# Sheet1.net
KiCad netlist of a schematic drawn in Altium Designer
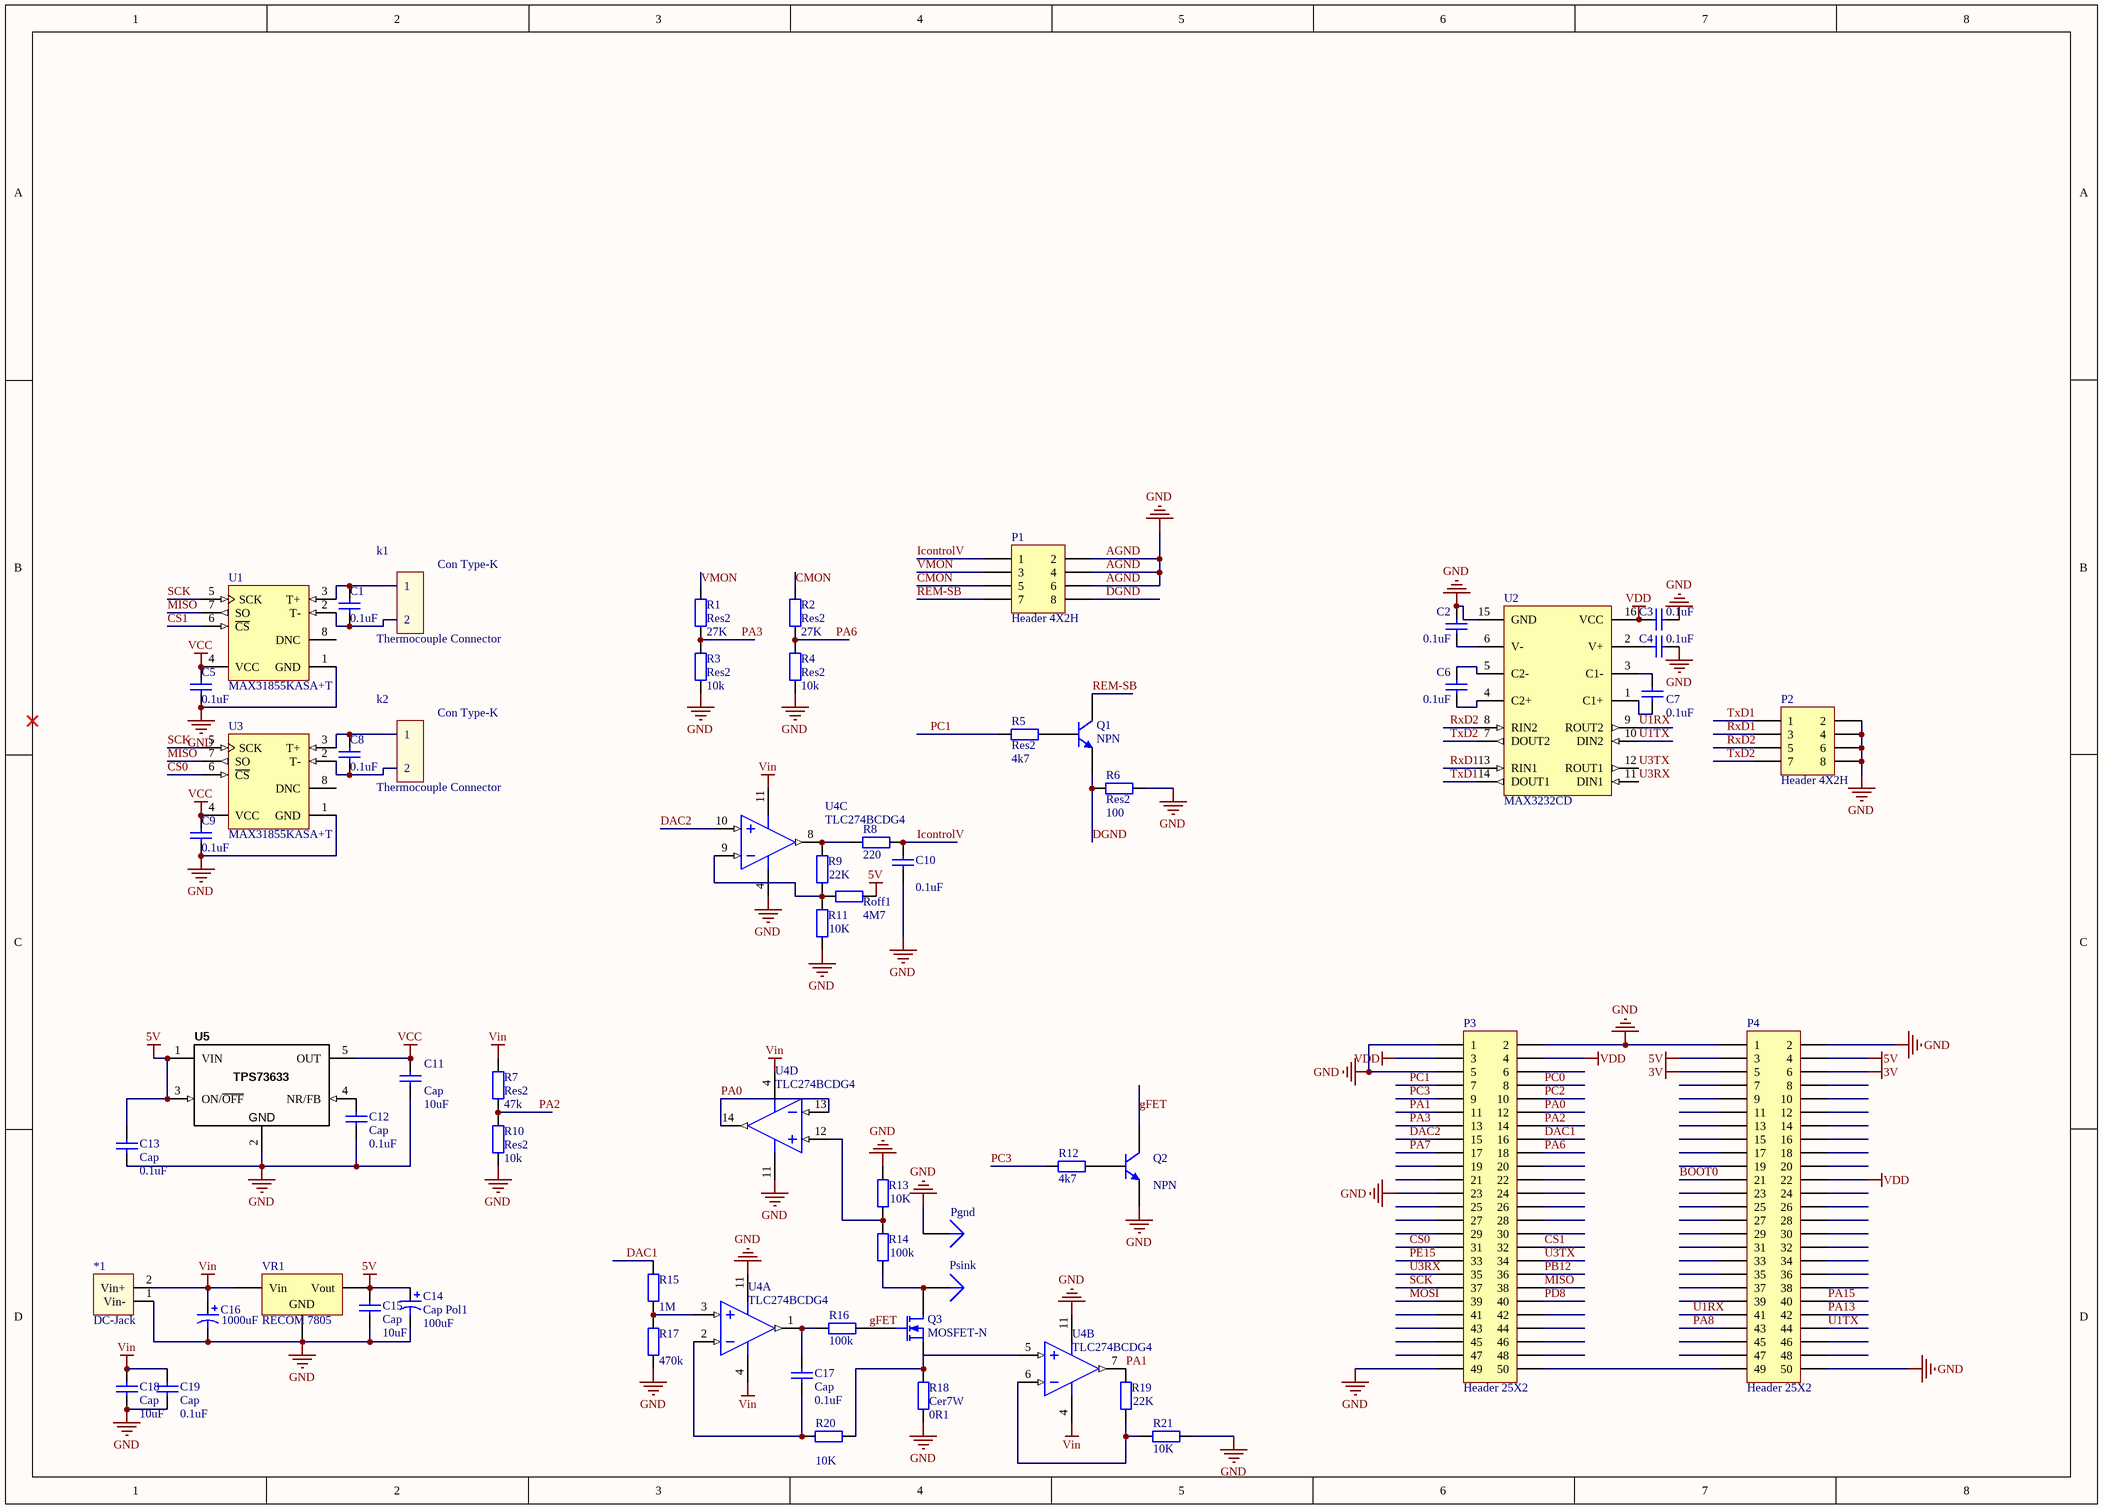
[diagram p0: Sheet1.SchDoc]

(export (version "E")
  (design (tool "Eeschema 10.0.6"))
  (components
    (comp (ref "*1")
      (value "DC-Jack")
      (footprint "DC-Jack")
      (libsource (lib "SchematicLib") (part "DC-Jack"))
    )
    (comp (ref "C1")
      (value "0.1uF")
      (footprint "CAPC2012X135N")
      (description "Capacitor")
      (fields (field (name "Comment") "Cap") (field (name "PUBLISHER") "Altium Limited"))
      (libsource (lib "Miscellaneous Devices") (part "Cap"))
    )
    (comp (ref "C2")
      (value "0.1uF")
      (footprint "CAPC2012X135N")
      (description "Capacitor")
      (fields (field (name "Comment") "Cap") (field (name "PUBLISHER") "Altium Limited"))
      (libsource (lib "Miscellaneous Devices") (part "Cap"))
    )
    (comp (ref "C3")
      (value "0.1uF")
      (footprint "CAPC2012X135N")
      (description "Capacitor")
      (fields (field (name "Comment") "Cap") (field (name "PUBLISHER") "Altium Limited"))
      (libsource (lib "Miscellaneous Devices") (part "Cap"))
    )
    (comp (ref "C4")
      (value "0.1uF")
      (footprint "CAPC2012X135N")
      (description "Capacitor")
      (fields (field (name "Comment") "Cap") (field (name "PUBLISHER") "Altium Limited"))
      (libsource (lib "Miscellaneous Devices") (part "Cap"))
    )
    (comp (ref "C5")
      (value "0.1uF")
      (footprint "CAPC2012X135N")
      (description "Capacitor")
      (fields (field (name "Comment") "Cap") (field (name "PUBLISHER") "Altium Limited"))
      (libsource (lib "Miscellaneous Devices") (part "Cap"))
    )
    (comp (ref "C6")
      (value "0.1uF")
      (footprint "CAPC2012X135N")
      (description "Capacitor")
      (fields (field (name "Comment") "Cap") (field (name "PUBLISHER") "Altium Limited"))
      (libsource (lib "Miscellaneous Devices") (part "Cap"))
    )
    (comp (ref "C7")
      (value "0.1uF")
      (footprint "CAPC2012X135N")
      (description "Capacitor")
      (fields (field (name "Comment") "Cap") (field (name "PUBLISHER") "Altium Limited"))
      (libsource (lib "Miscellaneous Devices") (part "Cap"))
    )
    (comp (ref "C8")
      (value "0.1uF")
      (footprint "CAPC2012X135N")
      (description "Capacitor")
      (fields (field (name "Comment") "Cap") (field (name "PUBLISHER") "Altium Limited"))
      (libsource (lib "Miscellaneous Devices") (part "Cap"))
    )
    (comp (ref "C9")
      (value "0.1uF")
      (footprint "CAPC2012X135N")
      (description "Capacitor")
      (fields (field (name "Comment") "Cap") (field (name "PUBLISHER") "Altium Limited"))
      (libsource (lib "Miscellaneous Devices") (part "Cap"))
    )
    (comp (ref "C10")
      (value "0.1uF")
      (footprint "CAPC2012X135N")
      (description "Capacitor")
      (fields (field (name "Comment") "Cap") (field (name "PUBLISHER") "Altium Limited"))
      (libsource (lib "Miscellaneous Devices") (part "Cap"))
    )
    (comp (ref "C11")
      (value "Cap")
      (footprint "CAPC2012X135N")
      (description "Capacitor")
      (fields (field (name "ALTIUM_VALUE") "10uF") (field (name "PUBLISHER") "Altium Limited"))
      (libsource (lib "Miscellaneous Devices") (part "Cap"))
    )
    (comp (ref "C12")
      (value "Cap")
      (footprint "CAPC2012X135N")
      (description "Capacitor")
      (fields (field (name "ALTIUM_VALUE") "0.1uF") (field (name "PUBLISHER") "Altium Limited"))
      (libsource (lib "Miscellaneous Devices") (part "Cap"))
    )
    (comp (ref "C13")
      (value "Cap")
      (footprint "CAPC2012X135N")
      (description "Capacitor")
      (fields (field (name "ALTIUM_VALUE") "0.1uF") (field (name "PUBLISHER") "Altium Limited"))
      (libsource (lib "Miscellaneous Devices") (part "Cap"))
    )
    (comp (ref "C14")
      (value "Cap Pol1")
      (footprint "RB7.6-15")
      (description "Polarized Capacitor (Radial)")
      (fields (field (name "ALTIUM_VALUE") "100uF") (field (name "PUBLISHER") "Altium Limited"))
      (libsource (lib "Miscellaneous Devices") (part "Cap Pol1"))
    )
    (comp (ref "C15")
      (value "Cap")
      (footprint "CAPC2012X135N")
      (description "Capacitor")
      (fields (field (name "ALTIUM_VALUE") "10uF") (field (name "PUBLISHER") "Altium Limited"))
      (libsource (lib "Miscellaneous Devices") (part "Cap"))
    )
    (comp (ref "C16")
      (value "1000uF")
      (footprint "RB7.6-15")
      (description "Polarized Capacitor (Radial)")
      (fields (field (name "Comment") "Cap Pol1") (field (name "PUBLISHER") "Altium Limited"))
      (libsource (lib "Miscellaneous Devices") (part "Cap Pol1"))
    )
    (comp (ref "C17")
      (value "Cap")
      (footprint "CAPC2012X135N")
      (description "Capacitor")
      (fields (field (name "ALTIUM_VALUE") "0.1uF") (field (name "PUBLISHER") "Altium Limited"))
      (libsource (lib "Miscellaneous Devices") (part "Cap"))
    )
    (comp (ref "C18")
      (value "Cap")
      (footprint "CAPC2012X135N")
      (description "Capacitor")
      (fields (field (name "ALTIUM_VALUE") "10uF") (field (name "PUBLISHER") "Altium Limited"))
      (libsource (lib "Miscellaneous Devices") (part "Cap"))
    )
    (comp (ref "C19")
      (value "Cap")
      (footprint "CAPC2012X135N")
      (description "Capacitor")
      (fields (field (name "ALTIUM_VALUE") "0.1uF") (field (name "PUBLISHER") "Altium Limited"))
      (libsource (lib "Miscellaneous Devices") (part "Cap"))
    )
    (comp (ref "k1")
      (value "Thermocouple Connector")
      (footprint "K-Type Thermocouple Connector")
      (libsource (lib "SchematicLib") (part "Thermocouple Connector"))
    )
    (comp (ref "k2")
      (value "Thermocouple Connector")
      (footprint "K-Type Thermocouple Connector")
      (libsource (lib "SchematicLib") (part "Thermocouple Connector"))
    )
    (comp (ref "P1")
      (value "Header 4X2H")
      (footprint "CON8")
      (description "Header, 4-Pin, Dual row, Right Angle")
      (fields (field (name "PUBLISHER") "Altium Limited"))
      (libsource (lib "Miscellaneous Connectors") (part "Header 4X2H"))
    )
    (comp (ref "P2")
      (value "Header 4X2H")
      (footprint "CON8")
      (description "Header, 4-Pin, Dual row, Right Angle")
      (fields (field (name "PUBLISHER") "Altium Limited"))
      (libsource (lib "Miscellaneous Connectors") (part "Header 4X2H"))
    )
    (comp (ref "P3")
      (value "Header 25X2")
      (footprint "HDR2X25")
      (description "Header, 25-Pin, Dual row")
      (fields (field (name "PUBLISHER") "Altium Limited"))
      (libsource (lib "Miscellaneous Connectors") (part "Header 25X2"))
    )
    (comp (ref "P4")
      (value "Header 25X2")
      (footprint "HDR2X25")
      (description "Header, 25-Pin, Dual row")
      (fields (field (name "PUBLISHER") "Altium Limited"))
      (libsource (lib "Miscellaneous Connectors") (part "Header 25X2"))
    )
    (comp (ref "Pgnd")
      (value "Plug")
      (footprint "PIN1")
      (fields (field (name "PUBLISHER") "Altium Limited"))
      (libsource (lib "Miscellaneous Connectors") (part "Plug"))
    )
    (comp (ref "Psink")
      (value "Plug")
      (footprint "PIN1")
      (fields (field (name "PUBLISHER") "Altium Limited"))
      (libsource (lib "Miscellaneous Connectors") (part "Plug"))
    )
    (comp (ref "Q1")
      (value "NPN")
      (footprint "SOT-23_N")
      (description "NPN Bipolar Transistor")
      (fields (field (name "PUBLISHER") "Altium Limited"))
      (libsource (lib "Miscellaneous Devices") (part "NPN"))
    )
    (comp (ref "Q2")
      (value "NPN")
      (footprint "SOT-23_N")
      (description "NPN Bipolar Transistor")
      (fields (field (name "PUBLISHER") "Altium Limited"))
      (libsource (lib "Miscellaneous Devices") (part "NPN"))
    )
    (comp (ref "Q3")
      (value "MOSFET-N")
      (footprint "TO-220-AB")
      (description "N-Channel MOSFET")
      (fields (field (name "PUBLISHER") "Altium Limited"))
      (libsource (lib "Miscellaneous Devices") (part "MOSFET-N"))
    )
    (comp (ref "R1")
      (value "Res2")
      (footprint "RESC2012X70N")
      (description "Resistor")
      (fields (field (name "ALTIUM_VALUE") "27K") (field (name "PUBLISHER") "Altium Limited"))
      (libsource (lib "Miscellaneous Devices") (part "Res2"))
    )
    (comp (ref "R2")
      (value "Res2")
      (footprint "RESC2012X70N")
      (description "Resistor")
      (fields (field (name "ALTIUM_VALUE") "27K") (field (name "PUBLISHER") "Altium Limited"))
      (libsource (lib "Miscellaneous Devices") (part "Res2"))
    )
    (comp (ref "R3")
      (value "Res2")
      (footprint "RESC2012X70N")
      (description "Resistor")
      (fields (field (name "ALTIUM_VALUE") "10k") (field (name "PUBLISHER") "Altium Limited"))
      (libsource (lib "Miscellaneous Devices") (part "Res2"))
    )
    (comp (ref "R4")
      (value "Res2")
      (footprint "RESC2012X70N")
      (description "Resistor")
      (fields (field (name "ALTIUM_VALUE") "10k") (field (name "PUBLISHER") "Altium Limited"))
      (libsource (lib "Miscellaneous Devices") (part "Res2"))
    )
    (comp (ref "R5")
      (value "Res2")
      (footprint "RESC2012X70N")
      (description "Resistor")
      (fields (field (name "ALTIUM_VALUE") "4k7") (field (name "PUBLISHER") "Altium Limited"))
      (libsource (lib "") (part "Res2_1"))
    )
    (comp (ref "R6")
      (value "Res2")
      (footprint "RESC2012X70N")
      (description "Resistor")
      (fields (field (name "ALTIUM_VALUE") "100") (field (name "PUBLISHER") "Altium Limited"))
      (libsource (lib "") (part "Res2_1"))
    )
    (comp (ref "R7")
      (value "Res2")
      (footprint "RESC2012X70N")
      (description "Resistor")
      (fields (field (name "ALTIUM_VALUE") "47k") (field (name "PUBLISHER") "Altium Limited"))
      (libsource (lib "Miscellaneous Devices") (part "Res2"))
    )
    (comp (ref "R8")
      (value "220")
      (footprint "RESC2012X70N")
      (description "Resistor")
      (fields (field (name "Comment") "Res2") (field (name "PUBLISHER") "Altium Limited"))
      (libsource (lib "") (part "Res2_2"))
    )
    (comp (ref "R9")
      (value "22K")
      (footprint "RESC2012X70N")
      (description "Resistor")
      (fields (field (name "Comment") "Res2") (field (name "PUBLISHER") "Altium Limited"))
      (libsource (lib "Miscellaneous Devices") (part "Res2"))
    )
    (comp (ref "R10")
      (value "Res2")
      (footprint "RESC2012X70N")
      (description "Resistor")
      (fields (field (name "ALTIUM_VALUE") "10k") (field (name "PUBLISHER") "Altium Limited"))
      (libsource (lib "Miscellaneous Devices") (part "Res2"))
    )
    (comp (ref "R11")
      (value "10K")
      (footprint "RESC2012X70N")
      (description "Resistor")
      (fields (field (name "Comment") "Res2") (field (name "PUBLISHER") "Altium Limited"))
      (libsource (lib "Miscellaneous Devices") (part "Res2"))
    )
    (comp (ref "R12")
      (value "4k7")
      (footprint "RESC2012X70N")
      (description "Resistor")
      (fields (field (name "Comment") "Res2") (field (name "PUBLISHER") "Altium Limited"))
      (libsource (lib "") (part "Res2_1"))
    )
    (comp (ref "R13")
      (value "10K")
      (footprint "RESC2012X70N")
      (description "Resistor")
      (fields (field (name "Comment") "Res2") (field (name "PUBLISHER") "Altium Limited"))
      (libsource (lib "Miscellaneous Devices") (part "Res2"))
    )
    (comp (ref "R14")
      (value "100k")
      (footprint "RESC2012X70N")
      (description "Resistor")
      (fields (field (name "Comment") "Res2") (field (name "PUBLISHER") "Altium Limited"))
      (libsource (lib "Miscellaneous Devices") (part "Res2"))
    )
    (comp (ref "R15")
      (value "1M")
      (footprint "RESC2012X70N")
      (description "Resistor")
      (fields (field (name "Comment") "Res2") (field (name "PUBLISHER") "Altium Limited"))
      (libsource (lib "Miscellaneous Devices") (part "Res2"))
    )
    (comp (ref "R16")
      (value "100k")
      (footprint "RESC2012X70N")
      (description "Resistor")
      (fields (field (name "Comment") "Res2") (field (name "PUBLISHER") "Altium Limited"))
      (libsource (lib "") (part "Res2_2"))
    )
    (comp (ref "R17")
      (value "470k")
      (footprint "RESC2012X70N")
      (description "Resistor")
      (fields (field (name "Comment") "Res2") (field (name "PUBLISHER") "Altium Limited"))
      (libsource (lib "Miscellaneous Devices") (part "Res2"))
    )
    (comp (ref "R18")
      (value "Cer7W")
      (footprint "Cer7W")
      (description "Resistor")
      (fields (field (name "ALTIUM_VALUE") "0R1") (field (name "PUBLISHER") "Altium Limited"))
      (libsource (lib "Miscellaneous Devices") (part "Res2"))
    )
    (comp (ref "R19")
      (value "22K")
      (footprint "RESC2012X70N")
      (description "Resistor")
      (fields (field (name "Comment") "Res2") (field (name "PUBLISHER") "Altium Limited"))
      (libsource (lib "Miscellaneous Devices") (part "Res2"))
    )
    (comp (ref "R20")
      (value "10K")
      (footprint "RESC2012X70N")
      (description "Resistor")
      (fields (field (name "Comment") "Res2") (field (name "PUBLISHER") "Altium Limited"))
      (libsource (lib "") (part "Res2_2"))
    )
    (comp (ref "R21")
      (value "10K")
      (footprint "RESC2012X70N")
      (description "Resistor")
      (fields (field (name "Comment") "Res2") (field (name "PUBLISHER") "Altium Limited"))
      (libsource (lib "") (part "Res2_1"))
    )
    (comp (ref "Roff1")
      (value "4M7")
      (footprint "RESC2012X70N")
      (description "Resistor")
      (fields (field (name "Comment") "Res2") (field (name "PUBLISHER") "Altium Limited"))
      (libsource (lib "") (part "Res2_1"))
    )
    (comp (ref "U1")
      (value "MAX31855KASA+T")
      (footprint "MAXM-S8+4_N")
      (fields (field (name "GENERIC PART NUMBER") "MAX31855"))
      (libsource (lib "Maxim Sensors") (part "MAX31855KASA+T"))
    )
    (comp (ref "U2")
      (value "MAX3232CD")
      (footprint "TI-D16_N")
      (libsource (lib "Texas Instruments Interface RS-232") (part "MAX3232CD"))
    )
    (comp (ref "U3")
      (value "MAX31855KASA+T")
      (footprint "MAXM-S8+4_N")
      (fields (field (name "GENERIC PART NUMBER") "MAX31855"))
      (libsource (lib "Maxim Sensors") (part "MAX31855KASA+T"))
    )
    (comp (ref "U4")
      (value "TLC274BCDG4")
      (footprint "TI-D14_N")
      (fields (field (name "MANUFACTURER") "Texas Instruments"))
      (libsource (lib "TI Amplifiers and Linear Operational Amplifier General Purpose") (part "TLC274BCDG4"))
    )
    (comp (ref "U5")
      (value "3.3V")
      (footprint "SOT23-5")
      (description "IC LDO Regulator 3.3V 400mA SOT23-5 SMD")
      (fields (field (name "TOLERANCE") "±0.5%"))
      (libsource (lib "PBL - Regulators") (part "LinREG_3V3_400mA_TPS73633DBV"))
    )
    (comp (ref "VR1")
      (value "RECOM 7805")
      (footprint "Recom78xx")
      (description "Voltage Regulator")
      (fields (field (name "PUBLISHER") "Altium Limited"))
      (libsource (lib "SchematicLib") (part "Volt Reg"))
    )
  )
  (nets
    (net (code "1") (name "/BOOT0") (class "Default")
      (node (ref "P4") (pin "21") (pinfunction "21_21") (pintype "passive"))
    )
    (net (code "2") (name "/CMON") (class "Default")
      (node (ref "P1") (pin "5") (pinfunction "5_5") (pintype "passive"))
      (node (ref "R2") (pin "2") (pinfunction "2_2") (pintype "passive"))
    )
    (net (code "3") (name "/CS0") (class "Default")
      (node (ref "P3") (pin "31") (pinfunction "31_31") (pintype "passive"))
      (node (ref "U3") (pin "6") (pinfunction "~{CS}_6") (pintype "input"))
    )
    (net (code "4") (name "/CS1") (class "Default")
      (node (ref "P3") (pin "32") (pinfunction "32_32") (pintype "passive"))
      (node (ref "U1") (pin "6") (pinfunction "~{CS}_6") (pintype "input"))
    )
    (net (code "5") (name "/DAC1") (class "Default")
      (node (ref "P3") (pin "16") (pinfunction "16_16") (pintype "passive"))
      (node (ref "R15") (pin "2") (pinfunction "2_2") (pintype "passive"))
    )
    (net (code "6") (name "/DAC2") (class "Default")
      (node (ref "P3") (pin "15") (pinfunction "15_15") (pintype "passive"))
      (node (ref "U4") (pin "10") (pinfunction "IN3+_10") (pintype "input"))
    )
    (net (code "7") (name "/DGND") (class "Default")
      (node (ref "P1") (pin "8") (pinfunction "8_8") (pintype "passive"))
      (node (ref "Q1") (pin "3") (pinfunction "E_3") (pintype "passive"))
      (node (ref "R6") (pin "2") (pinfunction "2_2") (pintype "passive"))
    )
    (net (code "8") (name "/IcontrolV") (class "Default")
      (node (ref "C10") (pin "2") (pinfunction "2_2") (pintype "passive"))
      (node (ref "P1") (pin "1") (pinfunction "1_1") (pintype "passive"))
      (node (ref "R8") (pin "2") (pinfunction "2_2") (pintype "passive"))
    )
    (net (code "9") (name "/MISO") (class "Default")
      (node (ref "P3") (pin "38") (pinfunction "38_38") (pintype "passive"))
      (node (ref "U1") (pin "7") (pinfunction "SO_7") (pintype "output"))
      (node (ref "U3") (pin "7") (pinfunction "SO_7") (pintype "output"))
    )
    (net (code "10") (name "/MOSI") (class "Default")
      (node (ref "P3") (pin "39") (pinfunction "39_39") (pintype "passive"))
    )
    (net (code "11") (name "/PA0") (class "Default")
      (node (ref "P3") (pin "12") (pinfunction "12_12") (pintype "passive"))
      (node (ref "U4") (pin "13") (pinfunction "IN4-_13") (pintype "input"))
      (node (ref "U4") (pin "14") (pinfunction "OUT4_14") (pintype "output"))
    )
    (net (code "12") (name "/PA1") (class "Default")
      (node (ref "P3") (pin "11") (pinfunction "11_11") (pintype "passive"))
      (node (ref "R19") (pin "2") (pinfunction "2_2") (pintype "passive"))
      (node (ref "U4") (pin "7") (pinfunction "OUT2_7") (pintype "output"))
    )
    (net (code "13") (name "/PA2") (class "Default")
      (node (ref "P3") (pin "14") (pinfunction "14_14") (pintype "passive"))
      (node (ref "R10") (pin "2") (pinfunction "2_2") (pintype "passive"))
      (node (ref "R7") (pin "1") (pinfunction "1_1") (pintype "passive"))
    )
    (net (code "14") (name "/PA3") (class "Default")
      (node (ref "P3") (pin "13") (pinfunction "13_13") (pintype "passive"))
      (node (ref "R1") (pin "1") (pinfunction "1_1") (pintype "passive"))
      (node (ref "R3") (pin "2") (pinfunction "2_2") (pintype "passive"))
    )
    (net (code "15") (name "/PA6") (class "Default")
      (node (ref "P3") (pin "18") (pinfunction "18_18") (pintype "passive"))
      (node (ref "R2") (pin "1") (pinfunction "1_1") (pintype "passive"))
      (node (ref "R4") (pin "2") (pinfunction "2_2") (pintype "passive"))
    )
    (net (code "16") (name "/PA7") (class "Default")
      (node (ref "P3") (pin "17") (pinfunction "17_17") (pintype "passive"))
    )
    (net (code "17") (name "/PA8") (class "Default")
      (node (ref "P4") (pin "43") (pinfunction "43_43") (pintype "passive"))
    )
    (net (code "18") (name "/PA13") (class "Default")
      (node (ref "P4") (pin "42") (pinfunction "42_42") (pintype "passive"))
    )
    (net (code "19") (name "/PA15") (class "Default")
      (node (ref "P4") (pin "40") (pinfunction "40_40") (pintype "passive"))
    )
    (net (code "20") (name "/PB12") (class "Default")
      (node (ref "P3") (pin "36") (pinfunction "36_36") (pintype "passive"))
    )
    (net (code "21") (name "/PC0") (class "Default")
      (node (ref "P3") (pin "8") (pinfunction "8_8") (pintype "passive"))
    )
    (net (code "22") (name "/PC1") (class "Default")
      (node (ref "P3") (pin "7") (pinfunction "7_7") (pintype "passive"))
      (node (ref "R5") (pin "2") (pinfunction "2_2") (pintype "passive"))
    )
    (net (code "23") (name "/PC2") (class "Default")
      (node (ref "P3") (pin "10") (pinfunction "10_10") (pintype "passive"))
    )
    (net (code "24") (name "/PC3") (class "Default")
      (node (ref "P3") (pin "9") (pinfunction "9_9") (pintype "passive"))
      (node (ref "R12") (pin "2") (pinfunction "2_2") (pintype "passive"))
    )
    (net (code "25") (name "/PD8") (class "Default")
      (node (ref "P3") (pin "40") (pinfunction "40_40") (pintype "passive"))
    )
    (net (code "26") (name "/PE15") (class "Default")
      (node (ref "P3") (pin "33") (pinfunction "33_33") (pintype "passive"))
    )
    (net (code "27") (name "/REM-SB") (class "Default")
      (node (ref "P1") (pin "7") (pinfunction "7_7") (pintype "passive"))
      (node (ref "Q1") (pin "1") (pinfunction "C_1") (pintype "passive"))
    )
    (net (code "28") (name "/RxD1") (class "Default")
      (node (ref "P2") (pin "3") (pinfunction "3_3") (pintype "passive"))
      (node (ref "U2") (pin "13") (pinfunction "RIN1_13") (pintype "input"))
    )
    (net (code "29") (name "/RxD2") (class "Default")
      (node (ref "P2") (pin "5") (pinfunction "5_5") (pintype "passive"))
      (node (ref "U2") (pin "8") (pinfunction "RIN2_8") (pintype "input"))
    )
    (net (code "30") (name "/SCK") (class "Default")
      (node (ref "P3") (pin "37") (pinfunction "37_37") (pintype "passive"))
      (node (ref "U1") (pin "5") (pinfunction "SCK_5") (pintype "input"))
      (node (ref "U3") (pin "5") (pinfunction "SCK_5") (pintype "input"))
    )
    (net (code "31") (name "/TxD1") (class "Default")
      (node (ref "P2") (pin "1") (pinfunction "1_1") (pintype "passive"))
      (node (ref "U2") (pin "14") (pinfunction "DOUT1_14") (pintype "output"))
    )
    (net (code "32") (name "/TxD2") (class "Default")
      (node (ref "P2") (pin "7") (pinfunction "7_7") (pintype "passive"))
      (node (ref "U2") (pin "7") (pinfunction "DOUT2_7") (pintype "output"))
    )
    (net (code "33") (name "/U1RX") (class "Default")
      (node (ref "P4") (pin "41") (pinfunction "41_41") (pintype "passive"))
      (node (ref "U2") (pin "9") (pinfunction "ROUT2_9") (pintype "output"))
    )
    (net (code "34") (name "/U1TX") (class "Default")
      (node (ref "P4") (pin "44") (pinfunction "44_44") (pintype "passive"))
      (node (ref "U2") (pin "10") (pinfunction "DIN2_10") (pintype "input"))
    )
    (net (code "35") (name "/U3RX") (class "Default")
      (node (ref "P3") (pin "35") (pinfunction "35_35") (pintype "passive"))
      (node (ref "U2") (pin "11") (pinfunction "DIN1_11") (pintype "input"))
    )
    (net (code "36") (name "/U3TX") (class "Default")
      (node (ref "P3") (pin "34") (pinfunction "34_34") (pintype "passive"))
      (node (ref "U2") (pin "12") (pinfunction "ROUT1_12") (pintype "output"))
    )
    (net (code "37") (name "/VMON") (class "Default")
      (node (ref "P1") (pin "3") (pinfunction "3_3") (pintype "passive"))
      (node (ref "R1") (pin "2") (pinfunction "2_2") (pintype "passive"))
    )
    (net (code "38") (name "/gFET") (class "Default")
      (node (ref "Q2") (pin "1") (pinfunction "C_1") (pintype "passive"))
      (node (ref "Q3") (pin "2") (pinfunction "G_2") (pintype "passive"))
      (node (ref "R16") (pin "2") (pinfunction "2_2") (pintype "passive"))
    )
    (net (code "39") (name "3V") (class "Default")
      (node (ref "P4") (pin "5") (pinfunction "5_5") (pintype "passive"))
      (node (ref "P4") (pin "6") (pinfunction "6_6") (pintype "passive"))
    )
    (net (code "40") (name "5V") (class "Default")
      (node (ref "C13") (pin "2") (pinfunction "2_2") (pintype "passive"))
      (node (ref "C14") (pin "1") (pinfunction "1_1") (pintype "passive"))
      (node (ref "C15") (pin "2") (pinfunction "2_2") (pintype "passive"))
      (node (ref "P4") (pin "3") (pinfunction "3_3") (pintype "passive"))
      (node (ref "P4") (pin "4") (pinfunction "4_4") (pintype "passive"))
      (node (ref "Roff1") (pin "1") (pinfunction "1_1") (pintype "passive"))
      (node (ref "U5") (pin "1") (pinfunction "VIN_1") (pintype "power_in"))
      (node (ref "U5") (pin "3") (pinfunction "ON/~{OFF}_3") (pintype "input"))
      (node (ref "VR1") (pin "3") (pinfunction "Vout_3") (pintype "passive"))
    )
    (net (code "41") (name "GND") (class "Default")
      (node (ref "*1") (pin "1") (pinfunction "Vin-_1") (pintype "passive"))
      (node (ref "C10") (pin "1") (pinfunction "1_1") (pintype "passive"))
      (node (ref "C11") (pin "1") (pinfunction "1_1") (pintype "passive"))
      (node (ref "C12") (pin "1") (pinfunction "1_1") (pintype "passive"))
      (node (ref "C13") (pin "1") (pinfunction "1_1") (pintype "passive"))
      (node (ref "C14") (pin "2") (pinfunction "2_2") (pintype "passive"))
      (node (ref "C15") (pin "1") (pinfunction "1_1") (pintype "passive"))
      (node (ref "C16") (pin "2") (pinfunction "2_2") (pintype "passive"))
      (node (ref "C18") (pin "1") (pinfunction "1_1") (pintype "passive"))
      (node (ref "C19") (pin "1") (pinfunction "1_1") (pintype "passive"))
      (node (ref "C2") (pin "2") (pinfunction "2_2") (pintype "passive"))
      (node (ref "C3") (pin "1") (pinfunction "1_1") (pintype "passive"))
      (node (ref "C4") (pin "1") (pinfunction "1_1") (pintype "passive"))
      (node (ref "C5") (pin "1") (pinfunction "1_1") (pintype "passive"))
      (node (ref "C9") (pin "1") (pinfunction "1_1") (pintype "passive"))
      (node (ref "P1") (pin "2") (pinfunction "2_2") (pintype "passive"))
      (node (ref "P1") (pin "4") (pinfunction "4_4") (pintype "passive"))
      (node (ref "P1") (pin "6") (pinfunction "6_6") (pintype "passive"))
      (node (ref "P2") (pin "2") (pinfunction "2_2") (pintype "passive"))
      (node (ref "P2") (pin "4") (pinfunction "4_4") (pintype "passive"))
      (node (ref "P2") (pin "6") (pinfunction "6_6") (pintype "passive"))
      (node (ref "P2") (pin "8") (pinfunction "8_8") (pintype "passive"))
      (node (ref "P3") (pin "1") (pinfunction "1_1") (pintype "passive"))
      (node (ref "P3") (pin "2") (pinfunction "2_2") (pintype "passive"))
      (node (ref "P3") (pin "23") (pinfunction "23_23") (pintype "passive"))
      (node (ref "P3") (pin "49") (pinfunction "49_49") (pintype "passive"))
      (node (ref "P3") (pin "5") (pinfunction "5_5") (pintype "passive"))
      (node (ref "P4") (pin "1") (pinfunction "1_1") (pintype "passive"))
      (node (ref "P4") (pin "2") (pinfunction "2_2") (pintype "passive"))
      (node (ref "P4") (pin "50") (pinfunction "50_50") (pintype "passive"))
      (node (ref "Pgnd") (pin "1") (pinfunction "1_1") (pintype "passive"))
      (node (ref "Q2") (pin "3") (pinfunction "E_3") (pintype "passive"))
      (node (ref "R10") (pin "1") (pinfunction "1_1") (pintype "passive"))
      (node (ref "R11") (pin "1") (pinfunction "1_1") (pintype "passive"))
      (node (ref "R13") (pin "2") (pinfunction "2_2") (pintype "passive"))
      (node (ref "R17") (pin "1") (pinfunction "1_1") (pintype "passive"))
      (node (ref "R18") (pin "1") (pinfunction "1_1") (pintype "passive"))
      (node (ref "R21") (pin "1") (pinfunction "1_1") (pintype "passive"))
      (node (ref "R3") (pin "1") (pinfunction "1_1") (pintype "passive"))
      (node (ref "R4") (pin "1") (pinfunction "1_1") (pintype "passive"))
      (node (ref "R6") (pin "1") (pinfunction "1_1") (pintype "passive"))
      (node (ref "U1") (pin "1") (pinfunction "GND_1") (pintype "power_in"))
      (node (ref "U2") (pin "15") (pinfunction "GND_15") (pintype "power_in"))
      (node (ref "U3") (pin "1") (pinfunction "GND_1") (pintype "power_in"))
      (node (ref "U4") (pin "11") (pinfunction "GND_11") (pintype "power_in"))
      (node (ref "U4") (pin "4") (pinfunction "VDD_4") (pintype "power_in"))
      (node (ref "U5") (pin "2") (pinfunction "GND_2") (pintype "power_in"))
      (node (ref "VR1") (pin "2") (pinfunction "GND_2") (pintype "passive"))
    )
    (net (code "42") (name "Net-(P3-Pad50)") (class "Default")
      (node (ref "P3") (pin "50") (pinfunction "50_50") (pintype "passive"))
      (node (ref "P4") (pin "49") (pinfunction "49_49") (pintype "passive"))
    )
    (net (code "43") (name "Net-(Q1-B)") (class "Default")
      (node (ref "Q1") (pin "2") (pinfunction "B_2") (pintype "passive"))
      (node (ref "R5") (pin "1") (pinfunction "1_1") (pintype "passive"))
    )
    (net (code "44") (name "Net-(Q2-B)") (class "Default")
      (node (ref "Q2") (pin "2") (pinfunction "B_2") (pintype "passive"))
      (node (ref "R12") (pin "1") (pinfunction "1_1") (pintype "passive"))
    )
    (net (code "45") (name "Net-(Q3-D)") (class "Default")
      (node (ref "Psink") (pin "1") (pinfunction "1_1") (pintype "passive"))
      (node (ref "Q3") (pin "1") (pinfunction "D_1") (pintype "passive"))
      (node (ref "R14") (pin "1") (pinfunction "1_1") (pintype "passive"))
    )
    (net (code "46") (name "Net-(Q3-S)") (class "Default")
      (node (ref "Q3") (pin "3") (pinfunction "S_3") (pintype "passive"))
      (node (ref "R18") (pin "2") (pinfunction "2_2") (pintype "passive"))
      (node (ref "R20") (pin "2") (pinfunction "2_2") (pintype "passive"))
      (node (ref "U4") (pin "5") (pinfunction "IN2+_5") (pintype "input"))
    )
    (net (code "47") (name "Net-(U1-T+)") (class "Default")
      (node (ref "C1") (pin "2") (pinfunction "2_2") (pintype "passive"))
      (node (ref "U1") (pin "3") (pinfunction "T+_3") (pintype "input"))
      (node (ref "k1") (pin "1") (pinfunction "1_1") (pintype "passive"))
    )
    (net (code "48") (name "Net-(U1-T-)") (class "Default")
      (node (ref "C1") (pin "1") (pinfunction "1_1") (pintype "passive"))
      (node (ref "U1") (pin "2") (pinfunction "T-_2") (pintype "input"))
      (node (ref "k1") (pin "2") (pinfunction "2_2") (pintype "passive"))
    )
    (net (code "49") (name "Net-(U2-C1+)") (class "Default")
      (node (ref "C7") (pin "1") (pinfunction "1_1") (pintype "passive"))
      (node (ref "U2") (pin "1") (pinfunction "C1+_1") (pintype "passive"))
    )
    (net (code "50") (name "Net-(U2-C1-)") (class "Default")
      (node (ref "C7") (pin "2") (pinfunction "2_2") (pintype "passive"))
      (node (ref "U2") (pin "3") (pinfunction "C1-_3") (pintype "passive"))
    )
    (net (code "51") (name "Net-(U2-C2+)") (class "Default")
      (node (ref "C6") (pin "1") (pinfunction "1_1") (pintype "passive"))
      (node (ref "U2") (pin "4") (pinfunction "C2+_4") (pintype "passive"))
    )
    (net (code "52") (name "Net-(U2-C2-)") (class "Default")
      (node (ref "C6") (pin "2") (pinfunction "2_2") (pintype "passive"))
      (node (ref "U2") (pin "5") (pinfunction "C2-_5") (pintype "passive"))
    )
    (net (code "53") (name "Net-(U2-V+)") (class "Default")
      (node (ref "C4") (pin "2") (pinfunction "2_2") (pintype "passive"))
      (node (ref "U2") (pin "2") (pinfunction "V+_2") (pintype "power_in"))
    )
    (net (code "54") (name "Net-(U2-V-)") (class "Default")
      (node (ref "C2") (pin "1") (pinfunction "1_1") (pintype "passive"))
      (node (ref "U2") (pin "6") (pinfunction "V-_6") (pintype "power_in"))
    )
    (net (code "55") (name "Net-(U3-T+)") (class "Default")
      (node (ref "C8") (pin "2") (pinfunction "2_2") (pintype "passive"))
      (node (ref "U3") (pin "3") (pinfunction "T+_3") (pintype "input"))
      (node (ref "k2") (pin "1") (pinfunction "1_1") (pintype "passive"))
    )
    (net (code "56") (name "Net-(U3-T-)") (class "Default")
      (node (ref "C8") (pin "1") (pinfunction "1_1") (pintype "passive"))
      (node (ref "U3") (pin "2") (pinfunction "T-_2") (pintype "input"))
      (node (ref "k2") (pin "2") (pinfunction "2_2") (pintype "passive"))
    )
    (net (code "57") (name "Net-(U4A-IN1+)") (class "Default")
      (node (ref "R15") (pin "1") (pinfunction "1_1") (pintype "passive"))
      (node (ref "R17") (pin "2") (pinfunction "2_2") (pintype "passive"))
      (node (ref "U4") (pin "3") (pinfunction "IN1+_3") (pintype "input"))
    )
    (net (code "58") (name "Net-(U4A-IN1-)") (class "Default")
      (node (ref "C17") (pin "1") (pinfunction "1_1") (pintype "passive"))
      (node (ref "R20") (pin "1") (pinfunction "1_1") (pintype "passive"))
      (node (ref "U4") (pin "2") (pinfunction "IN1-_2") (pintype "input"))
    )
    (net (code "59") (name "Net-(U4A-OUT1)") (class "Default")
      (node (ref "C17") (pin "2") (pinfunction "2_2") (pintype "passive"))
      (node (ref "R16") (pin "1") (pinfunction "1_1") (pintype "passive"))
      (node (ref "U4") (pin "1") (pinfunction "OUT1_1") (pintype "output"))
    )
    (net (code "60") (name "Net-(U4B-IN2-)") (class "Default")
      (node (ref "R19") (pin "1") (pinfunction "1_1") (pintype "passive"))
      (node (ref "R21") (pin "2") (pinfunction "2_2") (pintype "passive"))
      (node (ref "U4") (pin "6") (pinfunction "IN2-_6") (pintype "input"))
    )
    (net (code "61") (name "Net-(U4C-IN3-)") (class "Default")
      (node (ref "R11") (pin "2") (pinfunction "2_2") (pintype "passive"))
      (node (ref "R9") (pin "1") (pinfunction "1_1") (pintype "passive"))
      (node (ref "Roff1") (pin "2") (pinfunction "2_2") (pintype "passive"))
      (node (ref "U4") (pin "9") (pinfunction "IN3-_9") (pintype "input"))
    )
    (net (code "62") (name "Net-(U4C-OUT3)") (class "Default")
      (node (ref "R8") (pin "1") (pinfunction "1_1") (pintype "passive"))
      (node (ref "R9") (pin "2") (pinfunction "2_2") (pintype "passive"))
      (node (ref "U4") (pin "8") (pinfunction "OUT3_8") (pintype "output"))
    )
    (net (code "63") (name "Net-(U4D-IN4+)") (class "Default")
      (node (ref "R13") (pin "1") (pinfunction "1_1") (pintype "passive"))
      (node (ref "R14") (pin "2") (pinfunction "2_2") (pintype "passive"))
      (node (ref "U4") (pin "12") (pinfunction "IN4+_12") (pintype "input"))
    )
    (net (code "64") (name "Net-(U5-NR{slash}FB)") (class "Default")
      (node (ref "C12") (pin "2") (pinfunction "2_2") (pintype "passive"))
      (node (ref "U5") (pin "4") (pinfunction "NR/FB_4") (pintype "input"))
    )
    (net (code "65") (name "VCC") (class "Default")
      (node (ref "C11") (pin "2") (pinfunction "2_2") (pintype "passive"))
      (node (ref "C5") (pin "2") (pinfunction "2_2") (pintype "passive"))
      (node (ref "C9") (pin "2") (pinfunction "2_2") (pintype "passive"))
      (node (ref "U1") (pin "4") (pinfunction "VCC_4") (pintype "power_in"))
      (node (ref "U3") (pin "4") (pinfunction "VCC_4") (pintype "power_in"))
      (node (ref "U5") (pin "5") (pinfunction "OUT_5") (pintype "power_in"))
    )
    (net (code "66") (name "VDD") (class "Default")
      (node (ref "C3") (pin "2") (pinfunction "2_2") (pintype "passive"))
      (node (ref "P3") (pin "3") (pinfunction "3_3") (pintype "passive"))
      (node (ref "P3") (pin "4") (pinfunction "4_4") (pintype "passive"))
      (node (ref "P4") (pin "22") (pinfunction "22_22") (pintype "passive"))
      (node (ref "U2") (pin "16") (pinfunction "VCC_16") (pintype "power_in"))
    )
    (net (code "67") (name "Vin") (class "Default")
      (node (ref "*1") (pin "2") (pinfunction "Vin+_2") (pintype "passive"))
      (node (ref "C16") (pin "1") (pinfunction "1_1") (pintype "passive"))
      (node (ref "C18") (pin "2") (pinfunction "2_2") (pintype "passive"))
      (node (ref "C19") (pin "2") (pinfunction "2_2") (pintype "passive"))
      (node (ref "R7") (pin "2") (pinfunction "2_2") (pintype "passive"))
      (node (ref "U4") (pin "11") (pinfunction "GND_11") (pintype "power_in"))
      (node (ref "U4") (pin "4") (pinfunction "VDD_4") (pintype "power_in"))
      (node (ref "VR1") (pin "1") (pinfunction "Vin_1") (pintype "passive"))
    )
    (net (code "68") (name "unconnected-(P3-Pad6)") (class "Default")
      (node (ref "P3") (pin "6") (pinfunction "6_6") (pintype "passive"))
    )
    (net (code "69") (name "unconnected-(P3-Pad19)") (class "Default")
      (node (ref "P3") (pin "19") (pinfunction "19_19") (pintype "passive"))
    )
    (net (code "70") (name "unconnected-(P3-Pad20)") (class "Default")
      (node (ref "P3") (pin "20") (pinfunction "20_20") (pintype "passive"))
    )
    (net (code "71") (name "unconnected-(P3-Pad21)") (class "Default")
      (node (ref "P3") (pin "21") (pinfunction "21_21") (pintype "passive"))
    )
    (net (code "72") (name "unconnected-(P3-Pad22)") (class "Default")
      (node (ref "P3") (pin "22") (pinfunction "22_22") (pintype "passive"))
    )
    (net (code "73") (name "unconnected-(P3-Pad24)") (class "Default")
      (node (ref "P3") (pin "24") (pinfunction "24_24") (pintype "passive"))
    )
    (net (code "74") (name "unconnected-(P3-Pad25)") (class "Default")
      (node (ref "P3") (pin "25") (pinfunction "25_25") (pintype "passive"))
    )
    (net (code "75") (name "unconnected-(P3-Pad26)") (class "Default")
      (node (ref "P3") (pin "26") (pinfunction "26_26") (pintype "passive"))
    )
    (net (code "76") (name "unconnected-(P3-Pad27)") (class "Default")
      (node (ref "P3") (pin "27") (pinfunction "27_27") (pintype "passive"))
    )
    (net (code "77") (name "unconnected-(P3-Pad28)") (class "Default")
      (node (ref "P3") (pin "28") (pinfunction "28_28") (pintype "passive"))
    )
    (net (code "78") (name "unconnected-(P3-Pad29)") (class "Default")
      (node (ref "P3") (pin "29") (pinfunction "29_29") (pintype "passive"))
    )
    (net (code "79") (name "unconnected-(P3-Pad30)") (class "Default")
      (node (ref "P3") (pin "30") (pinfunction "30_30") (pintype "passive"))
    )
    (net (code "80") (name "unconnected-(P3-Pad41)") (class "Default")
      (node (ref "P3") (pin "41") (pinfunction "41_41") (pintype "passive"))
    )
    (net (code "81") (name "unconnected-(P3-Pad42)") (class "Default")
      (node (ref "P3") (pin "42") (pinfunction "42_42") (pintype "passive"))
    )
    (net (code "82") (name "unconnected-(P3-Pad43)") (class "Default")
      (node (ref "P3") (pin "43") (pinfunction "43_43") (pintype "passive"))
    )
    (net (code "83") (name "unconnected-(P3-Pad44)") (class "Default")
      (node (ref "P3") (pin "44") (pinfunction "44_44") (pintype "passive"))
    )
    (net (code "84") (name "unconnected-(P3-Pad45)") (class "Default")
      (node (ref "P3") (pin "45") (pinfunction "45_45") (pintype "passive"))
    )
    (net (code "85") (name "unconnected-(P3-Pad46)") (class "Default")
      (node (ref "P3") (pin "46") (pinfunction "46_46") (pintype "passive"))
    )
    (net (code "86") (name "unconnected-(P3-Pad47)") (class "Default")
      (node (ref "P3") (pin "47") (pinfunction "47_47") (pintype "passive"))
    )
    (net (code "87") (name "unconnected-(P3-Pad48)") (class "Default")
      (node (ref "P3") (pin "48") (pinfunction "48_48") (pintype "passive"))
    )
    (net (code "88") (name "unconnected-(P4-Pad7)") (class "Default")
      (node (ref "P4") (pin "7") (pinfunction "7_7") (pintype "passive"))
    )
    (net (code "89") (name "unconnected-(P4-Pad8)") (class "Default")
      (node (ref "P4") (pin "8") (pinfunction "8_8") (pintype "passive"))
    )
    (net (code "90") (name "unconnected-(P4-Pad9)") (class "Default")
      (node (ref "P4") (pin "9") (pinfunction "9_9") (pintype "passive"))
    )
    (net (code "91") (name "unconnected-(P4-Pad10)") (class "Default")
      (node (ref "P4") (pin "10") (pinfunction "10_10") (pintype "passive"))
    )
    (net (code "92") (name "unconnected-(P4-Pad11)") (class "Default")
      (node (ref "P4") (pin "11") (pinfunction "11_11") (pintype "passive"))
    )
    (net (code "93") (name "unconnected-(P4-Pad12)") (class "Default")
      (node (ref "P4") (pin "12") (pinfunction "12_12") (pintype "passive"))
    )
    (net (code "94") (name "unconnected-(P4-Pad13)") (class "Default")
      (node (ref "P4") (pin "13") (pinfunction "13_13") (pintype "passive"))
    )
    (net (code "95") (name "unconnected-(P4-Pad14)") (class "Default")
      (node (ref "P4") (pin "14") (pinfunction "14_14") (pintype "passive"))
    )
    (net (code "96") (name "unconnected-(P4-Pad15)") (class "Default")
      (node (ref "P4") (pin "15") (pinfunction "15_15") (pintype "passive"))
    )
    (net (code "97") (name "unconnected-(P4-Pad16)") (class "Default")
      (node (ref "P4") (pin "16") (pinfunction "16_16") (pintype "passive"))
    )
    (net (code "98") (name "unconnected-(P4-Pad17)") (class "Default")
      (node (ref "P4") (pin "17") (pinfunction "17_17") (pintype "passive"))
    )
    (net (code "99") (name "unconnected-(P4-Pad18)") (class "Default")
      (node (ref "P4") (pin "18") (pinfunction "18_18") (pintype "passive"))
    )
    (net (code "100") (name "unconnected-(P4-Pad19)") (class "Default")
      (node (ref "P4") (pin "19") (pinfunction "19_19") (pintype "passive"))
    )
    (net (code "101") (name "unconnected-(P4-Pad20)") (class "Default")
      (node (ref "P4") (pin "20") (pinfunction "20_20") (pintype "passive"))
    )
    (net (code "102") (name "unconnected-(P4-Pad23)") (class "Default")
      (node (ref "P4") (pin "23") (pinfunction "23_23") (pintype "passive"))
    )
    (net (code "103") (name "unconnected-(P4-Pad24)") (class "Default")
      (node (ref "P4") (pin "24") (pinfunction "24_24") (pintype "passive"))
    )
    (net (code "104") (name "unconnected-(P4-Pad25)") (class "Default")
      (node (ref "P4") (pin "25") (pinfunction "25_25") (pintype "passive"))
    )
    (net (code "105") (name "unconnected-(P4-Pad26)") (class "Default")
      (node (ref "P4") (pin "26") (pinfunction "26_26") (pintype "passive"))
    )
    (net (code "106") (name "unconnected-(P4-Pad27)") (class "Default")
      (node (ref "P4") (pin "27") (pinfunction "27_27") (pintype "passive"))
    )
    (net (code "107") (name "unconnected-(P4-Pad28)") (class "Default")
      (node (ref "P4") (pin "28") (pinfunction "28_28") (pintype "passive"))
    )
    (net (code "108") (name "unconnected-(P4-Pad29)") (class "Default")
      (node (ref "P4") (pin "29") (pinfunction "29_29") (pintype "passive"))
    )
    (net (code "109") (name "unconnected-(P4-Pad30)") (class "Default")
      (node (ref "P4") (pin "30") (pinfunction "30_30") (pintype "passive"))
    )
    (net (code "110") (name "unconnected-(P4-Pad31)") (class "Default")
      (node (ref "P4") (pin "31") (pinfunction "31_31") (pintype "passive"))
    )
    (net (code "111") (name "unconnected-(P4-Pad32)") (class "Default")
      (node (ref "P4") (pin "32") (pinfunction "32_32") (pintype "passive"))
    )
    (net (code "112") (name "unconnected-(P4-Pad33)") (class "Default")
      (node (ref "P4") (pin "33") (pinfunction "33_33") (pintype "passive"))
    )
    (net (code "113") (name "unconnected-(P4-Pad34)") (class "Default")
      (node (ref "P4") (pin "34") (pinfunction "34_34") (pintype "passive"))
    )
    (net (code "114") (name "unconnected-(P4-Pad35)") (class "Default")
      (node (ref "P4") (pin "35") (pinfunction "35_35") (pintype "passive"))
    )
    (net (code "115") (name "unconnected-(P4-Pad36)") (class "Default")
      (node (ref "P4") (pin "36") (pinfunction "36_36") (pintype "passive"))
    )
    (net (code "116") (name "unconnected-(P4-Pad37)") (class "Default")
      (node (ref "P4") (pin "37") (pinfunction "37_37") (pintype "passive"))
    )
    (net (code "117") (name "unconnected-(P4-Pad38)") (class "Default")
      (node (ref "P4") (pin "38") (pinfunction "38_38") (pintype "passive"))
    )
    (net (code "118") (name "unconnected-(P4-Pad39)") (class "Default")
      (node (ref "P4") (pin "39") (pinfunction "39_39") (pintype "passive"))
    )
    (net (code "119") (name "unconnected-(P4-Pad45)") (class "Default")
      (node (ref "P4") (pin "45") (pinfunction "45_45") (pintype "passive"))
    )
    (net (code "120") (name "unconnected-(P4-Pad46)") (class "Default")
      (node (ref "P4") (pin "46") (pinfunction "46_46") (pintype "passive"))
    )
    (net (code "121") (name "unconnected-(P4-Pad47)") (class "Default")
      (node (ref "P4") (pin "47") (pinfunction "47_47") (pintype "passive"))
    )
    (net (code "122") (name "unconnected-(P4-Pad48)") (class "Default")
      (node (ref "P4") (pin "48") (pinfunction "48_48") (pintype "passive"))
    )
    (net (code "123") (name "unconnected-(U1-DNC-Pad8)") (class "Default")
      (node (ref "U1") (pin "8") (pinfunction "DNC_8") (pintype "passive"))
    )
    (net (code "124") (name "unconnected-(U3-DNC-Pad8)") (class "Default")
      (node (ref "U3") (pin "8") (pinfunction "DNC_8") (pintype "passive"))
    )
  )
)
